# ControlBoardV2_PRO.net
KiCad netlist of a schematic drawn in EAGLE
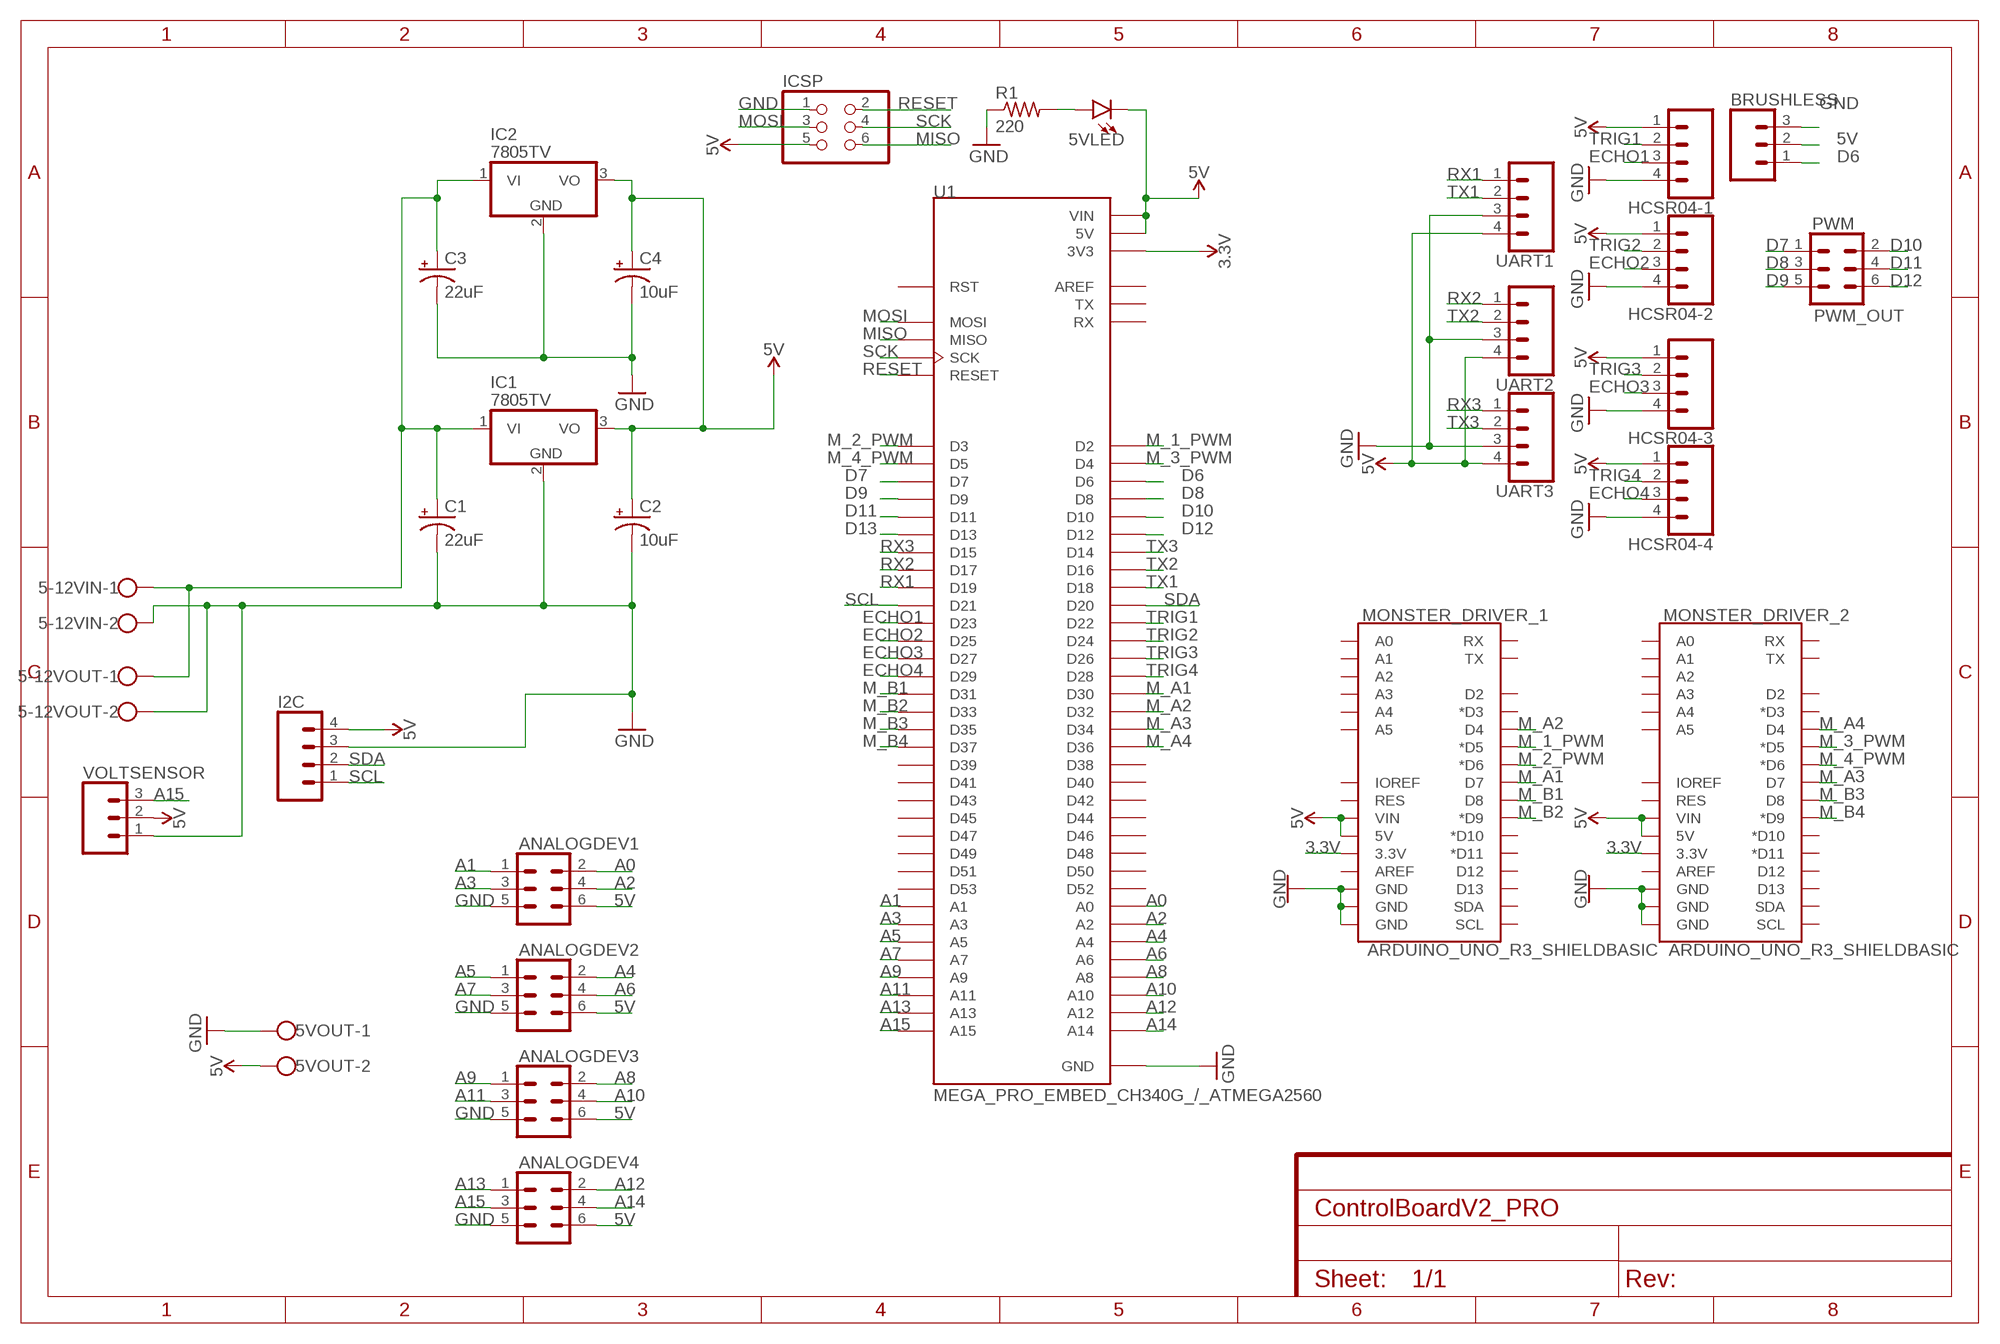
[diagram p0: schematic, sheet 1]

(export (version "E")
  (design (tool "Eeschema 10.0.6"))
  (components
    (comp (ref "5-12VIN")
      (value "W237-102")
      (footprint "eagle-import:W237-102")
      (fields (field (name "MPN") "237-102"))
      (libsource (lib "eagle-import") (part "W237-102"))
    )
    (comp (ref "5-12VOUT")
      (value "W237-102")
      (footprint "eagle-import:W237-102")
      (fields (field (name "MPN") "237-102"))
      (libsource (lib "eagle-import") (part "W237-102"))
    )
    (comp (ref "5VLED")
      (value "LED5MM")
      (footprint "eagle-import:LED_5MM")
      (libsource (lib "eagle-import") (part "LED5MM"))
    )
    (comp (ref "5VOUT")
      (value "W237-102")
      (footprint "eagle-import:W237-102")
      (fields (field (name "MPN") "237-102"))
      (libsource (lib "eagle-import") (part "W237-102"))
    )
    (comp (ref "ANALOGDEV1")
      (value "CONN_03X2NO_SILK")
      (footprint "eagle-import:2X3-NS")
      (libsource (lib "eagle-import") (part "SparkFun-Connectors_513_CONN_03X2NO_SILK"))
    )
    (comp (ref "ANALOGDEV2")
      (value "CONN_03X2NO_SILK")
      (footprint "eagle-import:2X3-NS")
      (libsource (lib "eagle-import") (part "SparkFun-Connectors_513_CONN_03X2NO_SILK"))
    )
    (comp (ref "ANALOGDEV3")
      (value "CONN_03X2NO_SILK")
      (footprint "eagle-import:2X3-NS")
      (libsource (lib "eagle-import") (part "SparkFun-Connectors_513_CONN_03X2NO_SILK"))
    )
    (comp (ref "ANALOGDEV4")
      (value "CONN_03X2NO_SILK")
      (footprint "eagle-import:2X3-NS")
      (libsource (lib "eagle-import") (part "SparkFun-Connectors_513_CONN_03X2NO_SILK"))
    )
    (comp (ref "BRUSHLESS")
      (value "CONN_03")
      (footprint "eagle-import:1X03")
      (libsource (lib "eagle-import") (part "CONN_03"))
    )
    (comp (ref "C1")
      (value "22uF")
      (footprint "eagle-import:E2,5-5")
      (libsource (lib "eagle-import") (part "CPOL-USE2.5-5"))
    )
    (comp (ref "C2")
      (value "10uF")
      (footprint "eagle-import:E2,5-5")
      (libsource (lib "eagle-import") (part "CPOL-USE2.5-5"))
    )
    (comp (ref "C3")
      (value "22uF")
      (footprint "eagle-import:E2,5-5")
      (libsource (lib "eagle-import") (part "CPOL-USE2.5-5"))
    )
    (comp (ref "C4")
      (value "10uF")
      (footprint "eagle-import:E2,5-5")
      (libsource (lib "eagle-import") (part "CPOL-USE2.5-5"))
    )
    (comp (ref "HCSR04-1")
      (value "CONN_04")
      (footprint "eagle-import:1X04")
      (libsource (lib "eagle-import") (part "CONN_04"))
    )
    (comp (ref "HCSR04-2")
      (value "CONN_04")
      (footprint "eagle-import:1X04")
      (libsource (lib "eagle-import") (part "CONN_04"))
    )
    (comp (ref "HCSR04-3")
      (value "CONN_04")
      (footprint "eagle-import:1X04")
      (libsource (lib "eagle-import") (part "CONN_04"))
    )
    (comp (ref "HCSR04-4")
      (value "CONN_04")
      (footprint "eagle-import:1X04")
      (libsource (lib "eagle-import") (part "CONN_04"))
    )
    (comp (ref "I2C")
      (value "CONN_04")
      (footprint "eagle-import:1X04")
      (libsource (lib "eagle-import") (part "CONN_04"))
    )
    (comp (ref "IC1")
      (value "7805TV")
      (footprint "eagle-import:TO220V")
      (libsource (lib "eagle-import") (part "78TV05"))
    )
    (comp (ref "IC2")
      (value "7805TV")
      (footprint "eagle-import:TO220V")
      (libsource (lib "eagle-import") (part "78TV05"))
    )
    (comp (ref "ICSP")
      (value "PINHD-2X3")
      (footprint "eagle-import:2X03")
      (libsource (lib "eagle-import") (part "PINHD-2X3"))
    )
    (comp (ref "MONSTER_DRIVER_1")
      (value "ARDUINO_UNO_R3_SHIELDBASIC")
      (footprint "eagle-import:UNO_R3_SHIELD")
      (libsource (lib "eagle-import") (part "ARDUINO_UNO_R3_SHIELDBASIC"))
    )
    (comp (ref "MONSTER_DRIVER_2")
      (value "ARDUINO_UNO_R3_SHIELDBASIC")
      (footprint "eagle-import:UNO_R3_SHIELD")
      (libsource (lib "eagle-import") (part "ARDUINO_UNO_R3_SHIELDBASIC"))
    )
    (comp (ref "PWM")
      (value "PWM_OUT")
      (footprint "eagle-import:2X3")
      (libsource (lib "eagle-import") (part "CONN_03X2FEMALE"))
    )
    (comp (ref "R1")
      (value "220")
      (footprint "eagle-import:0204_7")
      (libsource (lib "eagle-import") (part "R-US_0204/7"))
    )
    (comp (ref "U1")
      (value "MEGA_PRO_EMBED_CH340G_/_ATMEGA2560")
      (footprint "eagle-import:MODULE_MEGA_PRO_EMBED_CH340G___ATMEGA2560")
      (fields (field (name "MF") "Robotdyn") (field (name "MP") "Mega Pro Embed CH340G / ATmega2560"))
      (libsource (lib "eagle-import") (part "MEGA_PRO_EMBED_CH340G_/_ATMEGA2560"))
    )
    (comp (ref "UART1")
      (value "CONN_04")
      (footprint "eagle-import:1X04")
      (libsource (lib "eagle-import") (part "CONN_04"))
    )
    (comp (ref "UART2")
      (value "CONN_04")
      (footprint "eagle-import:1X04")
      (libsource (lib "eagle-import") (part "CONN_04"))
    )
    (comp (ref "UART3")
      (value "CONN_04")
      (footprint "eagle-import:1X04")
      (libsource (lib "eagle-import") (part "CONN_04"))
    )
    (comp (ref "VOLTSENSOR")
      (value "CONN_03")
      (footprint "eagle-import:1X03")
      (libsource (lib "eagle-import") (part "SparkFun-Connectors_513_CONN_03"))
    )
  )
  (nets
    (net (code "1") (name "/A0") (class "Default")
      (node (ref "ANALOGDEV1") (pin "2") (pinfunction "2_2") (pintype "bidirectional"))
      (node (ref "U1") (pin "A0") (pinfunction "A0_A0") (pintype "bidirectional"))
    )
    (net (code "2") (name "/A1") (class "Default")
      (node (ref "ANALOGDEV1") (pin "1") (pinfunction "1_1") (pintype "bidirectional"))
      (node (ref "U1") (pin "A1") (pinfunction "A1_A1") (pintype "bidirectional"))
    )
    (net (code "3") (name "/A2") (class "Default")
      (node (ref "ANALOGDEV1") (pin "4") (pinfunction "4_4") (pintype "bidirectional"))
      (node (ref "U1") (pin "A2") (pinfunction "A2_A2") (pintype "bidirectional"))
    )
    (net (code "4") (name "/A3") (class "Default")
      (node (ref "ANALOGDEV1") (pin "3") (pinfunction "3_3") (pintype "bidirectional"))
      (node (ref "U1") (pin "A3") (pinfunction "A3_A3") (pintype "bidirectional"))
    )
    (net (code "5") (name "/A4") (class "Default")
      (node (ref "ANALOGDEV2") (pin "2") (pinfunction "2_2") (pintype "bidirectional"))
      (node (ref "U1") (pin "A4") (pinfunction "A4_A4") (pintype "bidirectional"))
    )
    (net (code "6") (name "/A5") (class "Default")
      (node (ref "ANALOGDEV2") (pin "1") (pinfunction "1_1") (pintype "bidirectional"))
      (node (ref "U1") (pin "A5") (pinfunction "A5_A5") (pintype "bidirectional"))
    )
    (net (code "7") (name "/A6") (class "Default")
      (node (ref "ANALOGDEV2") (pin "4") (pinfunction "4_4") (pintype "bidirectional"))
      (node (ref "U1") (pin "A6") (pinfunction "A6_A6") (pintype "bidirectional"))
    )
    (net (code "8") (name "/A7") (class "Default")
      (node (ref "ANALOGDEV2") (pin "3") (pinfunction "3_3") (pintype "bidirectional"))
      (node (ref "U1") (pin "A7") (pinfunction "A7_A7") (pintype "bidirectional"))
    )
    (net (code "9") (name "/A8") (class "Default")
      (node (ref "ANALOGDEV3") (pin "2") (pinfunction "2_2") (pintype "bidirectional"))
      (node (ref "U1") (pin "A8") (pinfunction "A8_A8") (pintype "bidirectional"))
    )
    (net (code "10") (name "/A9") (class "Default")
      (node (ref "ANALOGDEV3") (pin "1") (pinfunction "1_1") (pintype "bidirectional"))
      (node (ref "U1") (pin "A9") (pinfunction "A9_A9") (pintype "bidirectional"))
    )
    (net (code "11") (name "/A10") (class "Default")
      (node (ref "ANALOGDEV3") (pin "4") (pinfunction "4_4") (pintype "bidirectional"))
      (node (ref "U1") (pin "A10") (pinfunction "A10_A10") (pintype "bidirectional"))
    )
    (net (code "12") (name "/A11") (class "Default")
      (node (ref "ANALOGDEV3") (pin "3") (pinfunction "3_3") (pintype "bidirectional"))
      (node (ref "U1") (pin "A11") (pinfunction "A11_A11") (pintype "bidirectional"))
    )
    (net (code "13") (name "/A12") (class "Default")
      (node (ref "ANALOGDEV4") (pin "2") (pinfunction "2_2") (pintype "bidirectional"))
      (node (ref "U1") (pin "A12") (pinfunction "A12_A12") (pintype "bidirectional"))
    )
    (net (code "14") (name "/A13") (class "Default")
      (node (ref "ANALOGDEV4") (pin "1") (pinfunction "1_1") (pintype "bidirectional"))
      (node (ref "U1") (pin "A13") (pinfunction "A13_A13") (pintype "bidirectional"))
    )
    (net (code "15") (name "/A14") (class "Default")
      (node (ref "ANALOGDEV4") (pin "4") (pinfunction "4_4") (pintype "bidirectional"))
      (node (ref "U1") (pin "A14") (pinfunction "A14_A14") (pintype "bidirectional"))
    )
    (net (code "16") (name "/A15") (class "Default")
      (node (ref "ANALOGDEV4") (pin "3") (pinfunction "3_3") (pintype "bidirectional"))
      (node (ref "U1") (pin "A15") (pinfunction "A15_A15") (pintype "bidirectional"))
      (node (ref "VOLTSENSOR") (pin "3") (pinfunction "3_3") (pintype "passive"))
    )
    (net (code "17") (name "/D6") (class "Default")
      (node (ref "BRUSHLESS") (pin "1") (pinfunction "1_1") (pintype "passive"))
      (node (ref "U1") (pin "D6") (pinfunction "D6_D6") (pintype "bidirectional"))
    )
    (net (code "18") (name "/D7") (class "Default")
      (node (ref "PWM") (pin "1") (pinfunction "1_1") (pintype "bidirectional"))
      (node (ref "U1") (pin "D7") (pinfunction "D7_D7") (pintype "bidirectional"))
    )
    (net (code "19") (name "/D8") (class "Default")
      (node (ref "PWM") (pin "3") (pinfunction "3_3") (pintype "bidirectional"))
      (node (ref "U1") (pin "D8") (pinfunction "D8_D8") (pintype "bidirectional"))
    )
    (net (code "20") (name "/D9") (class "Default")
      (node (ref "PWM") (pin "5") (pinfunction "5_5") (pintype "bidirectional"))
      (node (ref "U1") (pin "D9") (pinfunction "D9_D9") (pintype "bidirectional"))
    )
    (net (code "21") (name "/D10") (class "Default")
      (node (ref "PWM") (pin "2") (pinfunction "2_2") (pintype "bidirectional"))
      (node (ref "U1") (pin "D10") (pinfunction "D10_D10") (pintype "bidirectional"))
    )
    (net (code "22") (name "/D11") (class "Default")
      (node (ref "PWM") (pin "4") (pinfunction "4_4") (pintype "bidirectional"))
      (node (ref "U1") (pin "D11") (pinfunction "D11_D11") (pintype "bidirectional"))
    )
    (net (code "23") (name "/D12") (class "Default")
      (node (ref "PWM") (pin "6") (pinfunction "6_6") (pintype "bidirectional"))
      (node (ref "U1") (pin "D12") (pinfunction "D12_D12") (pintype "bidirectional"))
    )
    (net (code "24") (name "/D13") (class "Default")
      (node (ref "U1") (pin "D13") (pinfunction "D13_D13") (pintype "bidirectional"))
    )
    (net (code "25") (name "/ECHO1") (class "Default")
      (node (ref "HCSR04-1") (pin "3") (pinfunction "3_3") (pintype "passive"))
      (node (ref "U1") (pin "D23") (pinfunction "D23_D23") (pintype "bidirectional"))
    )
    (net (code "26") (name "/ECHO2") (class "Default")
      (node (ref "HCSR04-2") (pin "3") (pinfunction "3_3") (pintype "passive"))
      (node (ref "U1") (pin "D25") (pinfunction "D25_D25") (pintype "bidirectional"))
    )
    (net (code "27") (name "/ECHO3") (class "Default")
      (node (ref "HCSR04-3") (pin "3") (pinfunction "3_3") (pintype "passive"))
      (node (ref "U1") (pin "D27") (pinfunction "D27_D27") (pintype "bidirectional"))
    )
    (net (code "28") (name "/ECHO4") (class "Default")
      (node (ref "HCSR04-4") (pin "3") (pinfunction "3_3") (pintype "passive"))
      (node (ref "U1") (pin "D29") (pinfunction "D29_D29") (pintype "bidirectional"))
    )
    (net (code "29") (name "/MISO") (class "Default")
      (node (ref "ICSP") (pin "6") (pinfunction "6_6") (pintype "passive"))
      (node (ref "U1") (pin "MISO") (pinfunction "MISO_MISO") (pintype "bidirectional"))
    )
    (net (code "30") (name "/MOSI") (class "Default")
      (node (ref "ICSP") (pin "3") (pinfunction "3_3") (pintype "passive"))
      (node (ref "U1") (pin "MOSI") (pinfunction "MOSI_MOSI") (pintype "bidirectional"))
    )
    (net (code "31") (name "/M_1_PWM") (class "Default")
      (node (ref "MONSTER_DRIVER_1") (pin "D5") (pinfunction "*D5_D5") (pintype "bidirectional"))
      (node (ref "U1") (pin "D2") (pinfunction "D2_D2") (pintype "bidirectional"))
    )
    (net (code "32") (name "/M_2_PWM") (class "Default")
      (node (ref "MONSTER_DRIVER_1") (pin "D6") (pinfunction "*D6_D6") (pintype "bidirectional"))
      (node (ref "U1") (pin "D3") (pinfunction "D3_D3") (pintype "bidirectional"))
    )
    (net (code "33") (name "/M_3_PWM") (class "Default")
      (node (ref "MONSTER_DRIVER_2") (pin "D5") (pinfunction "*D5_D5") (pintype "bidirectional"))
      (node (ref "U1") (pin "D4") (pinfunction "D4_D4") (pintype "bidirectional"))
    )
    (net (code "34") (name "/M_4_PWM") (class "Default")
      (node (ref "MONSTER_DRIVER_2") (pin "D6") (pinfunction "*D6_D6") (pintype "bidirectional"))
      (node (ref "U1") (pin "D5") (pinfunction "D5_D5") (pintype "bidirectional"))
    )
    (net (code "35") (name "/M_A1") (class "Default")
      (node (ref "MONSTER_DRIVER_1") (pin "D7") (pinfunction "D7_D7") (pintype "bidirectional"))
      (node (ref "U1") (pin "D30") (pinfunction "D30_D30") (pintype "bidirectional"))
    )
    (net (code "36") (name "/M_A2") (class "Default")
      (node (ref "MONSTER_DRIVER_1") (pin "D4") (pinfunction "D4_D4") (pintype "bidirectional"))
      (node (ref "U1") (pin "D32") (pinfunction "D32_D32") (pintype "bidirectional"))
    )
    (net (code "37") (name "/M_A3") (class "Default")
      (node (ref "MONSTER_DRIVER_2") (pin "D7") (pinfunction "D7_D7") (pintype "bidirectional"))
      (node (ref "U1") (pin "D34") (pinfunction "D34_D34") (pintype "bidirectional"))
    )
    (net (code "38") (name "/M_A4") (class "Default")
      (node (ref "MONSTER_DRIVER_2") (pin "D4") (pinfunction "D4_D4") (pintype "bidirectional"))
      (node (ref "U1") (pin "D36") (pinfunction "D36_D36") (pintype "bidirectional"))
    )
    (net (code "39") (name "/M_B1") (class "Default")
      (node (ref "MONSTER_DRIVER_1") (pin "D8") (pinfunction "D8_D8") (pintype "bidirectional"))
      (node (ref "U1") (pin "D31") (pinfunction "D31_D31") (pintype "bidirectional"))
    )
    (net (code "40") (name "/M_B2") (class "Default")
      (node (ref "MONSTER_DRIVER_1") (pin "D9") (pinfunction "*D9_D9") (pintype "bidirectional"))
      (node (ref "U1") (pin "D33") (pinfunction "D33_D33") (pintype "bidirectional"))
    )
    (net (code "41") (name "/M_B3") (class "Default")
      (node (ref "MONSTER_DRIVER_2") (pin "D8") (pinfunction "D8_D8") (pintype "bidirectional"))
      (node (ref "U1") (pin "D35") (pinfunction "D35_D35") (pintype "bidirectional"))
    )
    (net (code "42") (name "/M_B4") (class "Default")
      (node (ref "MONSTER_DRIVER_2") (pin "D9") (pinfunction "*D9_D9") (pintype "bidirectional"))
      (node (ref "U1") (pin "D37") (pinfunction "D37_D37") (pintype "bidirectional"))
    )
    (net (code "43") (name "/RESET") (class "Default")
      (node (ref "ICSP") (pin "2") (pinfunction "2_2") (pintype "passive"))
      (node (ref "U1") (pin "RESET") (pinfunction "RESET_RESET") (pintype "input"))
    )
    (net (code "44") (name "/RX1") (class "Default")
      (node (ref "U1") (pin "D19") (pinfunction "D19_D19") (pintype "bidirectional"))
      (node (ref "UART1") (pin "1") (pinfunction "1_1") (pintype "passive"))
    )
    (net (code "45") (name "/RX2") (class "Default")
      (node (ref "U1") (pin "D17") (pinfunction "D17_D17") (pintype "bidirectional"))
      (node (ref "UART2") (pin "1") (pinfunction "1_1") (pintype "passive"))
    )
    (net (code "46") (name "/RX3") (class "Default")
      (node (ref "U1") (pin "D15") (pinfunction "D15_D15") (pintype "bidirectional"))
      (node (ref "UART3") (pin "1") (pinfunction "1_1") (pintype "passive"))
    )
    (net (code "47") (name "/SCK") (class "Default")
      (node (ref "ICSP") (pin "4") (pinfunction "4_4") (pintype "passive"))
      (node (ref "U1") (pin "SCK") (pinfunction "SCK_SCK") (pintype "bidirectional"))
    )
    (net (code "48") (name "/SCL") (class "Default")
      (node (ref "I2C") (pin "1") (pinfunction "1_1") (pintype "passive"))
      (node (ref "U1") (pin "D21") (pinfunction "D21_D21") (pintype "bidirectional"))
    )
    (net (code "49") (name "/SDA") (class "Default")
      (node (ref "I2C") (pin "2") (pinfunction "2_2") (pintype "passive"))
      (node (ref "U1") (pin "D20") (pinfunction "D20_D20") (pintype "bidirectional"))
    )
    (net (code "50") (name "/TRIG1") (class "Default")
      (node (ref "HCSR04-1") (pin "2") (pinfunction "2_2") (pintype "passive"))
      (node (ref "U1") (pin "D22") (pinfunction "D22_D22") (pintype "bidirectional"))
    )
    (net (code "51") (name "/TRIG2") (class "Default")
      (node (ref "HCSR04-2") (pin "2") (pinfunction "2_2") (pintype "passive"))
      (node (ref "U1") (pin "D24") (pinfunction "D24_D24") (pintype "bidirectional"))
    )
    (net (code "52") (name "/TRIG3") (class "Default")
      (node (ref "HCSR04-3") (pin "2") (pinfunction "2_2") (pintype "passive"))
      (node (ref "U1") (pin "D26") (pinfunction "D26_D26") (pintype "bidirectional"))
    )
    (net (code "53") (name "/TRIG4") (class "Default")
      (node (ref "HCSR04-4") (pin "2") (pinfunction "2_2") (pintype "passive"))
      (node (ref "U1") (pin "D28") (pinfunction "D28_D28") (pintype "bidirectional"))
    )
    (net (code "54") (name "/TX1") (class "Default")
      (node (ref "U1") (pin "D18") (pinfunction "D18_D18") (pintype "bidirectional"))
      (node (ref "UART1") (pin "2") (pinfunction "2_2") (pintype "passive"))
    )
    (net (code "55") (name "/TX2") (class "Default")
      (node (ref "U1") (pin "D16") (pinfunction "D16_D16") (pintype "bidirectional"))
      (node (ref "UART2") (pin "2") (pinfunction "2_2") (pintype "passive"))
    )
    (net (code "56") (name "/TX3") (class "Default")
      (node (ref "U1") (pin "D14") (pinfunction "D14_D14") (pintype "bidirectional"))
      (node (ref "UART3") (pin "2") (pinfunction "2_2") (pintype "passive"))
    )
    (net (code "57") (name "3.3V") (class "Default")
      (node (ref "MONSTER_DRIVER_1") (pin "3.3V") (pinfunction "3.3V_3.3V") (pintype "bidirectional"))
      (node (ref "MONSTER_DRIVER_2") (pin "3.3V") (pinfunction "3.3V_3.3V") (pintype "bidirectional"))
      (node (ref "U1") (pin "3V3_1") (pinfunction "3V3_3V3_1") (pintype "power_in"))
      (node (ref "U1") (pin "3V3_2") (pinfunction "3V3_3V3_2") (pintype "power_in"))
    )
    (net (code "58") (name "5V") (class "Default")
      (node (ref "5VLED") (pin "K") (pinfunction "C_K") (pintype "passive"))
      (node (ref "5VOUT") (pin "2") (pinfunction "KL_2") (pintype "passive"))
      (node (ref "ANALOGDEV1") (pin "6") (pinfunction "6_6") (pintype "bidirectional"))
      (node (ref "ANALOGDEV2") (pin "6") (pinfunction "6_6") (pintype "bidirectional"))
      (node (ref "ANALOGDEV3") (pin "6") (pinfunction "6_6") (pintype "bidirectional"))
      (node (ref "ANALOGDEV4") (pin "6") (pinfunction "6_6") (pintype "bidirectional"))
      (node (ref "BRUSHLESS") (pin "2") (pinfunction "2_2") (pintype "passive"))
      (node (ref "C2") (pin "+") (pinfunction "+_+") (pintype "passive"))
      (node (ref "C4") (pin "+") (pinfunction "+_+") (pintype "passive"))
      (node (ref "HCSR04-1") (pin "1") (pinfunction "1_1") (pintype "passive"))
      (node (ref "HCSR04-2") (pin "1") (pinfunction "1_1") (pintype "passive"))
      (node (ref "HCSR04-3") (pin "1") (pinfunction "1_1") (pintype "passive"))
      (node (ref "HCSR04-4") (pin "1") (pinfunction "1_1") (pintype "passive"))
      (node (ref "I2C") (pin "4") (pinfunction "4_4") (pintype "passive"))
      (node (ref "IC1") (pin "3") (pinfunction "VO_3") (pintype "passive"))
      (node (ref "IC2") (pin "3") (pinfunction "VO_3") (pintype "passive"))
      (node (ref "ICSP") (pin "5") (pinfunction "5_5") (pintype "passive"))
      (node (ref "MONSTER_DRIVER_1") (pin "5V") (pinfunction "5V_5V") (pintype "bidirectional"))
      (node (ref "MONSTER_DRIVER_1") (pin "VIN") (pinfunction "VIN_VIN") (pintype "bidirectional"))
      (node (ref "MONSTER_DRIVER_2") (pin "5V") (pinfunction "5V_5V") (pintype "bidirectional"))
      (node (ref "MONSTER_DRIVER_2") (pin "VIN") (pinfunction "VIN_VIN") (pintype "bidirectional"))
      (node (ref "U1") (pin "5V_1") (pinfunction "5V_5V_1") (pintype "power_in"))
      (node (ref "U1") (pin "5V_2") (pinfunction "5V_5V_2") (pintype "power_in"))
      (node (ref "U1") (pin "5V_3") (pinfunction "5V_5V_3") (pintype "power_in"))
      (node (ref "U1") (pin "VIN_1") (pinfunction "VIN_VIN_1") (pintype "power_in"))
      (node (ref "U1") (pin "VIN_2") (pinfunction "VIN_VIN_2") (pintype "power_in"))
      (node (ref "UART1") (pin "4") (pinfunction "4_4") (pintype "passive"))
      (node (ref "UART2") (pin "4") (pinfunction "4_4") (pintype "passive"))
      (node (ref "UART3") (pin "4") (pinfunction "4_4") (pintype "passive"))
      (node (ref "VOLTSENSOR") (pin "2") (pinfunction "2_2") (pintype "passive"))
    )
    (net (code "59") (name "GND") (class "Default")
      (node (ref "5-12VIN") (pin "2") (pinfunction "KL_2") (pintype "passive"))
      (node (ref "5-12VOUT") (pin "2") (pinfunction "KL_2") (pintype "passive"))
      (node (ref "5VOUT") (pin "1") (pinfunction "KL_1") (pintype "passive"))
      (node (ref "ANALOGDEV1") (pin "5") (pinfunction "5_5") (pintype "bidirectional"))
      (node (ref "ANALOGDEV2") (pin "5") (pinfunction "5_5") (pintype "bidirectional"))
      (node (ref "ANALOGDEV3") (pin "5") (pinfunction "5_5") (pintype "bidirectional"))
      (node (ref "ANALOGDEV4") (pin "5") (pinfunction "5_5") (pintype "bidirectional"))
      (node (ref "BRUSHLESS") (pin "3") (pinfunction "3_3") (pintype "passive"))
      (node (ref "C1") (pin "-") (pinfunction "-_-") (pintype "passive"))
      (node (ref "C2") (pin "-") (pinfunction "-_-") (pintype "passive"))
      (node (ref "C3") (pin "-") (pinfunction "-_-") (pintype "passive"))
      (node (ref "C4") (pin "-") (pinfunction "-_-") (pintype "passive"))
      (node (ref "HCSR04-1") (pin "4") (pinfunction "4_4") (pintype "passive"))
      (node (ref "HCSR04-2") (pin "4") (pinfunction "4_4") (pintype "passive"))
      (node (ref "HCSR04-3") (pin "4") (pinfunction "4_4") (pintype "passive"))
      (node (ref "HCSR04-4") (pin "4") (pinfunction "4_4") (pintype "passive"))
      (node (ref "I2C") (pin "3") (pinfunction "3_3") (pintype "passive"))
      (node (ref "IC1") (pin "2") (pinfunction "GND_2") (pintype "passive"))
      (node (ref "IC2") (pin "2") (pinfunction "GND_2") (pintype "passive"))
      (node (ref "ICSP") (pin "1") (pinfunction "1_1") (pintype "passive"))
      (node (ref "MONSTER_DRIVER_1") (pin "GND@0") (pinfunction "GND_GND@0") (pintype "bidirectional"))
      (node (ref "MONSTER_DRIVER_1") (pin "GND@1") (pinfunction "GND_GND@1") (pintype "bidirectional"))
      (node (ref "MONSTER_DRIVER_1") (pin "GND@2") (pinfunction "GND_GND@2") (pintype "bidirectional"))
      (node (ref "MONSTER_DRIVER_2") (pin "GND@0") (pinfunction "GND_GND@0") (pintype "bidirectional"))
      (node (ref "MONSTER_DRIVER_2") (pin "GND@1") (pinfunction "GND_GND@1") (pintype "bidirectional"))
      (node (ref "MONSTER_DRIVER_2") (pin "GND@2") (pinfunction "GND_GND@2") (pintype "bidirectional"))
      (node (ref "R1") (pin "1") (pinfunction "1_1") (pintype "passive"))
      (node (ref "U1") (pin "GND_1") (pinfunction "GND_GND_1") (pintype "power_in"))
      (node (ref "U1") (pin "GND_2") (pinfunction "GND_GND_2") (pintype "power_in"))
      (node (ref "U1") (pin "GND_3") (pinfunction "GND_GND_3") (pintype "power_in"))
      (node (ref "UART1") (pin "3") (pinfunction "3_3") (pintype "passive"))
      (node (ref "UART2") (pin "3") (pinfunction "3_3") (pintype "passive"))
      (node (ref "UART3") (pin "3") (pinfunction "3_3") (pintype "passive"))
      (node (ref "VOLTSENSOR") (pin "1") (pinfunction "1_1") (pintype "passive"))
    )
    (net (code "60") (name "Net-(5-12VINA-KL)") (class "Default")
      (node (ref "5-12VIN") (pin "1") (pinfunction "KL_1") (pintype "passive"))
      (node (ref "5-12VOUT") (pin "1") (pinfunction "KL_1") (pintype "passive"))
      (node (ref "C1") (pin "+") (pinfunction "+_+") (pintype "passive"))
      (node (ref "C3") (pin "+") (pinfunction "+_+") (pintype "passive"))
      (node (ref "IC1") (pin "1") (pinfunction "VI_1") (pintype "input"))
      (node (ref "IC2") (pin "1") (pinfunction "VI_1") (pintype "input"))
    )
    (net (code "61") (name "Net-(5VLED-PadA)") (class "Default")
      (node (ref "5VLED") (pin "A") (pinfunction "A_A") (pintype "passive"))
      (node (ref "R1") (pin "2") (pinfunction "2_2") (pintype "passive"))
    )
    (net (code "62") (name "unconnected-(MONSTER_DRIVER_1-*D3-PadD3)") (class "Default")
      (node (ref "MONSTER_DRIVER_1") (pin "D3") (pinfunction "*D3_D3") (pintype "bidirectional"))
    )
    (net (code "63") (name "unconnected-(MONSTER_DRIVER_1-*D10-PadD10)") (class "Default")
      (node (ref "MONSTER_DRIVER_1") (pin "D10") (pinfunction "*D10_D10") (pintype "bidirectional"))
    )
    (net (code "64") (name "unconnected-(MONSTER_DRIVER_1-*D11-PadD11)") (class "Default")
      (node (ref "MONSTER_DRIVER_1") (pin "D11") (pinfunction "*D11_D11") (pintype "bidirectional"))
    )
    (net (code "65") (name "unconnected-(MONSTER_DRIVER_1-PadA0)") (class "Default")
      (node (ref "MONSTER_DRIVER_1") (pin "A0") (pinfunction "A0_A0") (pintype "bidirectional"))
    )
    (net (code "66") (name "unconnected-(MONSTER_DRIVER_1-PadA1)") (class "Default")
      (node (ref "MONSTER_DRIVER_1") (pin "A1") (pinfunction "A1_A1") (pintype "bidirectional"))
    )
    (net (code "67") (name "unconnected-(MONSTER_DRIVER_1-PadA2)") (class "Default")
      (node (ref "MONSTER_DRIVER_1") (pin "A2") (pinfunction "A2_A2") (pintype "bidirectional"))
    )
    (net (code "68") (name "unconnected-(MONSTER_DRIVER_1-PadA3)") (class "Default")
      (node (ref "MONSTER_DRIVER_1") (pin "A3") (pinfunction "A3_A3") (pintype "bidirectional"))
    )
    (net (code "69") (name "unconnected-(MONSTER_DRIVER_1-PadA4)") (class "Default")
      (node (ref "MONSTER_DRIVER_1") (pin "A4") (pinfunction "A4_A4") (pintype "bidirectional"))
    )
    (net (code "70") (name "unconnected-(MONSTER_DRIVER_1-PadA5)") (class "Default")
      (node (ref "MONSTER_DRIVER_1") (pin "A5") (pinfunction "A5_A5") (pintype "bidirectional"))
    )
    (net (code "71") (name "unconnected-(MONSTER_DRIVER_1-PadAREF)") (class "Default")
      (node (ref "MONSTER_DRIVER_1") (pin "AREF") (pinfunction "AREF_AREF") (pintype "bidirectional"))
    )
    (net (code "72") (name "unconnected-(MONSTER_DRIVER_1-PadD2)") (class "Default")
      (node (ref "MONSTER_DRIVER_1") (pin "D2") (pinfunction "D2_D2") (pintype "bidirectional"))
    )
    (net (code "73") (name "unconnected-(MONSTER_DRIVER_1-PadD12)") (class "Default")
      (node (ref "MONSTER_DRIVER_1") (pin "D12") (pinfunction "D12_D12") (pintype "bidirectional"))
    )
    (net (code "74") (name "unconnected-(MONSTER_DRIVER_1-PadD13)") (class "Default")
      (node (ref "MONSTER_DRIVER_1") (pin "D13") (pinfunction "D13_D13") (pintype "bidirectional"))
    )
    (net (code "75") (name "unconnected-(MONSTER_DRIVER_1-PadIOREF)") (class "Default")
      (node (ref "MONSTER_DRIVER_1") (pin "IOREF") (pinfunction "IOREF_IOREF") (pintype "bidirectional"))
    )
    (net (code "76") (name "unconnected-(MONSTER_DRIVER_1-PadRES)") (class "Default")
      (node (ref "MONSTER_DRIVER_1") (pin "RES") (pinfunction "RES_RES") (pintype "bidirectional"))
    )
    (net (code "77") (name "unconnected-(MONSTER_DRIVER_1-PadRX)") (class "Default")
      (node (ref "MONSTER_DRIVER_1") (pin "RX") (pinfunction "RX_RX") (pintype "bidirectional"))
    )
    (net (code "78") (name "unconnected-(MONSTER_DRIVER_1-PadSCL)") (class "Default")
      (node (ref "MONSTER_DRIVER_1") (pin "SCL") (pinfunction "SCL_SCL") (pintype "bidirectional"))
    )
    (net (code "79") (name "unconnected-(MONSTER_DRIVER_1-PadSDA)") (class "Default")
      (node (ref "MONSTER_DRIVER_1") (pin "SDA") (pinfunction "SDA_SDA") (pintype "bidirectional"))
    )
    (net (code "80") (name "unconnected-(MONSTER_DRIVER_1-PadTX)") (class "Default")
      (node (ref "MONSTER_DRIVER_1") (pin "TX") (pinfunction "TX_TX") (pintype "bidirectional"))
    )
    (net (code "81") (name "unconnected-(MONSTER_DRIVER_2-*D3-PadD3)") (class "Default")
      (node (ref "MONSTER_DRIVER_2") (pin "D3") (pinfunction "*D3_D3") (pintype "bidirectional"))
    )
    (net (code "82") (name "unconnected-(MONSTER_DRIVER_2-*D10-PadD10)") (class "Default")
      (node (ref "MONSTER_DRIVER_2") (pin "D10") (pinfunction "*D10_D10") (pintype "bidirectional"))
    )
    (net (code "83") (name "unconnected-(MONSTER_DRIVER_2-*D11-PadD11)") (class "Default")
      (node (ref "MONSTER_DRIVER_2") (pin "D11") (pinfunction "*D11_D11") (pintype "bidirectional"))
    )
    (net (code "84") (name "unconnected-(MONSTER_DRIVER_2-PadA0)") (class "Default")
      (node (ref "MONSTER_DRIVER_2") (pin "A0") (pinfunction "A0_A0") (pintype "bidirectional"))
    )
    (net (code "85") (name "unconnected-(MONSTER_DRIVER_2-PadA1)") (class "Default")
      (node (ref "MONSTER_DRIVER_2") (pin "A1") (pinfunction "A1_A1") (pintype "bidirectional"))
    )
    (net (code "86") (name "unconnected-(MONSTER_DRIVER_2-PadA2)") (class "Default")
      (node (ref "MONSTER_DRIVER_2") (pin "A2") (pinfunction "A2_A2") (pintype "bidirectional"))
    )
    (net (code "87") (name "unconnected-(MONSTER_DRIVER_2-PadA3)") (class "Default")
      (node (ref "MONSTER_DRIVER_2") (pin "A3") (pinfunction "A3_A3") (pintype "bidirectional"))
    )
    (net (code "88") (name "unconnected-(MONSTER_DRIVER_2-PadA4)") (class "Default")
      (node (ref "MONSTER_DRIVER_2") (pin "A4") (pinfunction "A4_A4") (pintype "bidirectional"))
    )
    (net (code "89") (name "unconnected-(MONSTER_DRIVER_2-PadA5)") (class "Default")
      (node (ref "MONSTER_DRIVER_2") (pin "A5") (pinfunction "A5_A5") (pintype "bidirectional"))
    )
    (net (code "90") (name "unconnected-(MONSTER_DRIVER_2-PadAREF)") (class "Default")
      (node (ref "MONSTER_DRIVER_2") (pin "AREF") (pinfunction "AREF_AREF") (pintype "bidirectional"))
    )
    (net (code "91") (name "unconnected-(MONSTER_DRIVER_2-PadD2)") (class "Default")
      (node (ref "MONSTER_DRIVER_2") (pin "D2") (pinfunction "D2_D2") (pintype "bidirectional"))
    )
    (net (code "92") (name "unconnected-(MONSTER_DRIVER_2-PadD12)") (class "Default")
      (node (ref "MONSTER_DRIVER_2") (pin "D12") (pinfunction "D12_D12") (pintype "bidirectional"))
    )
    (net (code "93") (name "unconnected-(MONSTER_DRIVER_2-PadD13)") (class "Default")
      (node (ref "MONSTER_DRIVER_2") (pin "D13") (pinfunction "D13_D13") (pintype "bidirectional"))
    )
    (net (code "94") (name "unconnected-(MONSTER_DRIVER_2-PadIOREF)") (class "Default")
      (node (ref "MONSTER_DRIVER_2") (pin "IOREF") (pinfunction "IOREF_IOREF") (pintype "bidirectional"))
    )
    (net (code "95") (name "unconnected-(MONSTER_DRIVER_2-PadRES)") (class "Default")
      (node (ref "MONSTER_DRIVER_2") (pin "RES") (pinfunction "RES_RES") (pintype "bidirectional"))
    )
    (net (code "96") (name "unconnected-(MONSTER_DRIVER_2-PadRX)") (class "Default")
      (node (ref "MONSTER_DRIVER_2") (pin "RX") (pinfunction "RX_RX") (pintype "bidirectional"))
    )
    (net (code "97") (name "unconnected-(MONSTER_DRIVER_2-PadSCL)") (class "Default")
      (node (ref "MONSTER_DRIVER_2") (pin "SCL") (pinfunction "SCL_SCL") (pintype "bidirectional"))
    )
    (net (code "98") (name "unconnected-(MONSTER_DRIVER_2-PadSDA)") (class "Default")
      (node (ref "MONSTER_DRIVER_2") (pin "SDA") (pinfunction "SDA_SDA") (pintype "bidirectional"))
    )
    (net (code "99") (name "unconnected-(MONSTER_DRIVER_2-PadTX)") (class "Default")
      (node (ref "MONSTER_DRIVER_2") (pin "TX") (pinfunction "TX_TX") (pintype "bidirectional"))
    )
    (net (code "100") (name "unconnected-(U1-PadAREF)") (class "Default")
      (node (ref "U1") (pin "AREF") (pinfunction "AREF_AREF") (pintype "bidirectional"))
    )
    (net (code "101") (name "unconnected-(U1-PadD38)") (class "Default")
      (node (ref "U1") (pin "D38") (pinfunction "D38_D38") (pintype "bidirectional"))
    )
    (net (code "102") (name "unconnected-(U1-PadD39)") (class "Default")
      (node (ref "U1") (pin "D39") (pinfunction "D39_D39") (pintype "bidirectional"))
    )
    (net (code "103") (name "unconnected-(U1-PadD40)") (class "Default")
      (node (ref "U1") (pin "D40") (pinfunction "D40_D40") (pintype "bidirectional"))
    )
    (net (code "104") (name "unconnected-(U1-PadD41)") (class "Default")
      (node (ref "U1") (pin "D41") (pinfunction "D41_D41") (pintype "bidirectional"))
    )
    (net (code "105") (name "unconnected-(U1-PadD42)") (class "Default")
      (node (ref "U1") (pin "D42") (pinfunction "D42_D42") (pintype "bidirectional"))
    )
    (net (code "106") (name "unconnected-(U1-PadD43)") (class "Default")
      (node (ref "U1") (pin "D43") (pinfunction "D43_D43") (pintype "bidirectional"))
    )
    (net (code "107") (name "unconnected-(U1-PadD44)") (class "Default")
      (node (ref "U1") (pin "D44") (pinfunction "D44_D44") (pintype "bidirectional"))
    )
    (net (code "108") (name "unconnected-(U1-PadD45)") (class "Default")
      (node (ref "U1") (pin "D45") (pinfunction "D45_D45") (pintype "bidirectional"))
    )
    (net (code "109") (name "unconnected-(U1-PadD46)") (class "Default")
      (node (ref "U1") (pin "D46") (pinfunction "D46_D46") (pintype "bidirectional"))
    )
    (net (code "110") (name "unconnected-(U1-PadD47)") (class "Default")
      (node (ref "U1") (pin "D47") (pinfunction "D47_D47") (pintype "bidirectional"))
    )
    (net (code "111") (name "unconnected-(U1-PadD48)") (class "Default")
      (node (ref "U1") (pin "D48") (pinfunction "D48_D48") (pintype "bidirectional"))
    )
    (net (code "112") (name "unconnected-(U1-PadD49)") (class "Default")
      (node (ref "U1") (pin "D49") (pinfunction "D49_D49") (pintype "bidirectional"))
    )
    (net (code "113") (name "unconnected-(U1-PadD50)") (class "Default")
      (node (ref "U1") (pin "D50") (pinfunction "D50_D50") (pintype "bidirectional"))
    )
    (net (code "114") (name "unconnected-(U1-PadD51)") (class "Default")
      (node (ref "U1") (pin "D51") (pinfunction "D51_D51") (pintype "bidirectional"))
    )
    (net (code "115") (name "unconnected-(U1-PadD52)") (class "Default")
      (node (ref "U1") (pin "D52") (pinfunction "D52_D52") (pintype "bidirectional"))
    )
    (net (code "116") (name "unconnected-(U1-PadD53)") (class "Default")
      (node (ref "U1") (pin "D53") (pinfunction "D53_D53") (pintype "bidirectional"))
    )
    (net (code "117") (name "unconnected-(U1-PadRST)") (class "Default")
      (node (ref "U1") (pin "RST") (pinfunction "RST_RST") (pintype "input"))
    )
    (net (code "118") (name "unconnected-(U1-PadRX)") (class "Default")
      (node (ref "U1") (pin "RX") (pinfunction "RX_RX") (pintype "input"))
    )
    (net (code "119") (name "unconnected-(U1-PadTX)") (class "Default")
      (node (ref "U1") (pin "TX") (pinfunction "TX_TX") (pintype "output"))
    )
  )
)
